# Sheet1.net
KiCad netlist of a schematic drawn in Altium Designer
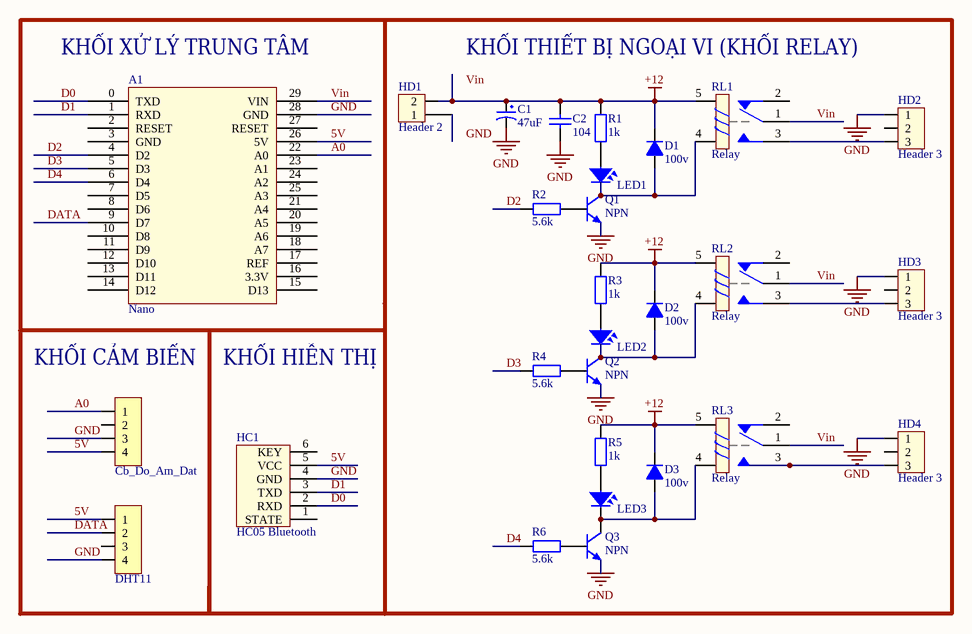
[diagram p0: Sheet1.SchDoc]

(export (version "E")
  (design (tool "Eeschema 10.0.6"))
  (components
    (comp (ref "A1")
      (value "Nano")
      (footprint "Arduino nano")
      (libsource (lib "Altium_Lib_by_KhueNguyenCreator") (part "Arduino Nano"))
    )
    (comp (ref "C1")
      (value "47uF")
      (footprint "tu hoa 5mm")
      (description "Cắm")
      (libsource (lib "Altium_Lib_by_KhueNguyenCreator") (part "Tu Hoa 47uF 25V 5x8"))
    )
    (comp (ref "C2")
      (value "104")
      (footprint "tu gom")
      (description "Cắm")
      (libsource (lib "Altium_Lib_by_KhueNguyenCreator") (part "Tu gom 104 50V"))
    )
    (comp (ref "D1")
      (value "100v")
      (footprint "DIODE 1A")
      (description "Cắm")
      (libsource (lib "Altium_Lib_by_KhueNguyenCreator") (part "Diode 1N4007"))
    )
    (comp (ref "D2")
      (value "100v")
      (footprint "DIODE 1A")
      (description "Cắm")
      (libsource (lib "Altium_Lib_by_KhueNguyenCreator") (part "Diode 1N4007"))
    )
    (comp (ref "D3")
      (value "100v")
      (footprint "DIODE 1A")
      (description "Cắm")
      (libsource (lib "Altium_Lib_by_KhueNguyenCreator") (part "Diode 1N4007"))
    )
    (comp (ref "HC1")
      (value "HC05 Bluetooth")
      (footprint "HC05 Bluethooth Dung")
      (description "Bluetooth HC05")
      (libsource (lib "Altium_Lib_by_KhueNguyenCreator") (part "HC05 Bluetooth"))
    )
    (comp (ref "HD1")
      (value "Header 2")
      (footprint "HED2")
      (description "Header 2 (Green)")
      (libsource (lib "syhaunguyen") (part "Hed2"))
    )
    (comp (ref "HD2")
      (value "Header 3")
      (footprint "HED3")
      (description "Header 3 (Green)")
      (libsource (lib "syhaunguyen") (part "Hed3"))
    )
    (comp (ref "HD3")
      (value "Header 3")
      (footprint "HED3")
      (description "Header 3 (Green)")
      (libsource (lib "syhaunguyen") (part "Hed3"))
    )
    (comp (ref "HD4")
      (value "Header 3")
      (footprint "HED3")
      (description "Header 3 (Green)")
      (libsource (lib "syhaunguyen") (part "Hed3"))
    )
    (comp (ref "JP3")
      (value "Cb_Do_Am_Dat")
      (footprint "JP 1x4 CT")
      (description "Cắm")
      (libsource (lib "Altium_Lib_by_KhueNguyenCreator") (part "JP 1x4 2.54 Cai Thang"))
    )
    (comp (ref "JP4")
      (value "DHT11")
      (footprint "JP 1x4 CT")
      (description "Cắm")
      (libsource (lib "Altium_Lib_by_KhueNguyenCreator") (part "JP 1x4 2.54 Cai Thang"))
    )
    (comp (ref "LED1")
      (value "LED")
      (footprint "LED-3")
      (description "LED Single colour Green and Red")
      (libsource (lib "syhaunguyen") (part "LED"))
    )
    (comp (ref "LED2")
      (value "LED")
      (footprint "LED-3")
      (description "LED Single colour Green and Red")
      (libsource (lib "syhaunguyen") (part "LED"))
    )
    (comp (ref "LED3")
      (value "LED")
      (footprint "LED-3")
      (description "LED Single colour Green and Red")
      (libsource (lib "syhaunguyen") (part "LED"))
    )
    (comp (ref "Q1")
      (value "NPN")
      (footprint "TRAN-LOWPOWER")
      (description "NPN General")
      (fields (field (name "PUBLISHER") "Altium Limited"))
      (libsource (lib "My library altium") (part "NPN"))
    )
    (comp (ref "Q2")
      (value "NPN")
      (footprint "TRAN-LOWPOWER")
      (description "NPN General")
      (fields (field (name "PUBLISHER") "Altium Limited"))
      (libsource (lib "My library altium") (part "NPN"))
    )
    (comp (ref "Q3")
      (value "NPN")
      (footprint "TRAN-LOWPOWER")
      (description "NPN General")
      (fields (field (name "PUBLISHER") "Altium Limited"))
      (libsource (lib "My library altium") (part "NPN"))
    )
    (comp (ref "R1")
      (value "1k")
      (footprint "tro vach 1/4w")
      (description "Cắm")
      (libsource (lib "Altium_Lib_by_KhueNguyenCreator") (part "Tro Vach 1/4W 5% 5.6k"))
    )
    (comp (ref "R2")
      (value "5.6k")
      (footprint "tro vach 1/4w")
      (description "Cắm")
      (libsource (lib "Altium_Lib_by_KhueNguyenCreator") (part "Tro Vach 1/4W 5% 5.6k"))
    )
    (comp (ref "R3")
      (value "1k")
      (footprint "tro vach 1/4w")
      (description "Cắm")
      (libsource (lib "Altium_Lib_by_KhueNguyenCreator") (part "Tro Vach 1/4W 5% 5.6k"))
    )
    (comp (ref "R4")
      (value "5.6k")
      (footprint "tro vach 1/4w")
      (description "Cắm")
      (libsource (lib "Altium_Lib_by_KhueNguyenCreator") (part "Tro Vach 1/4W 5% 5.6k"))
    )
    (comp (ref "R5")
      (value "1k")
      (footprint "tro vach 1/4w")
      (description "Cắm")
      (libsource (lib "Altium_Lib_by_KhueNguyenCreator") (part "Tro Vach 1/4W 5% 5.6k"))
    )
    (comp (ref "R6")
      (value "5.6k")
      (footprint "tro vach 1/4w")
      (description "Cắm")
      (libsource (lib "Altium_Lib_by_KhueNguyenCreator") (part "Tro Vach 1/4W 5% 5.6k"))
    )
    (comp (ref "RL1")
      (value "Relay")
      (footprint "Relay 5 Chan SRD")
      (description "Relay 5 Chan")
      (libsource (lib "Altium_Lib_by_KhueNguyenCreator") (part "Relay 5 Chan SRD"))
    )
    (comp (ref "RL2")
      (value "Relay")
      (footprint "Relay 5 Chan SRD")
      (description "Relay 5 Chan")
      (libsource (lib "Altium_Lib_by_KhueNguyenCreator") (part "Relay 5 Chan SRD"))
    )
    (comp (ref "RL3")
      (value "Relay")
      (footprint "Relay 5 Chan SRD")
      (description "Relay 5 Chan")
      (libsource (lib "Altium_Lib_by_KhueNguyenCreator") (part "Relay 5 Chan SRD"))
    )
  )
  (nets
    (net (code "1") (name "+12") (class "Default")
      (node (ref "C1") (pin "1") (pinfunction "1_1") (pintype "passive"))
      (node (ref "C2") (pin "1") (pinfunction "1_1") (pintype "passive"))
      (node (ref "D1") (pin "2") (pinfunction "K_2") (pintype "passive"))
      (node (ref "D2") (pin "2") (pinfunction "K_2") (pintype "passive"))
      (node (ref "D3") (pin "2") (pinfunction "K_2") (pintype "passive"))
      (node (ref "HD1") (pin "2") (pinfunction "2_2") (pintype "passive"))
      (node (ref "R1") (pin "1") (pinfunction "1_1") (pintype "passive"))
      (node (ref "R3") (pin "1") (pinfunction "1_1") (pintype "passive"))
      (node (ref "R5") (pin "1") (pinfunction "1_1") (pintype "passive"))
      (node (ref "RL1") (pin "5") (pinfunction "5_5") (pintype "passive"))
      (node (ref "RL2") (pin "5") (pinfunction "5_5") (pintype "passive"))
      (node (ref "RL3") (pin "5") (pinfunction "5_5") (pintype "passive"))
    )
    (net (code "2") (name "/5V") (class "Default")
      (node (ref "A1") (pin "26") (pinfunction "5V_26") (pintype "passive"))
      (node (ref "HC1") (pin "5") (pinfunction "VCC_5") (pintype "passive"))
      (node (ref "JP3") (pin "4") (pinfunction "4_4") (pintype "passive"))
      (node (ref "JP4") (pin "1") (pinfunction "1_1") (pintype "passive"))
    )
    (net (code "3") (name "/A0") (class "Default")
      (node (ref "A1") (pin "22") (pinfunction "A0_22") (pintype "passive"))
      (node (ref "JP3") (pin "1") (pinfunction "1_1") (pintype "passive"))
    )
    (net (code "4") (name "/D0") (class "Default")
      (node (ref "A1") (pin "0") (pinfunction "TXD_0") (pintype "passive"))
      (node (ref "HC1") (pin "2") (pinfunction "RXD_2") (pintype "passive"))
    )
    (net (code "5") (name "/D1") (class "Default")
      (node (ref "A1") (pin "1") (pinfunction "RXD_1") (pintype "passive"))
      (node (ref "HC1") (pin "3") (pinfunction "TXD_3") (pintype "passive"))
    )
    (net (code "6") (name "/D2") (class "Default")
      (node (ref "A1") (pin "4") (pinfunction "D2_4") (pintype "passive"))
      (node (ref "R2") (pin "2") (pinfunction "2_2") (pintype "passive"))
    )
    (net (code "7") (name "/D3") (class "Default")
      (node (ref "A1") (pin "5") (pinfunction "D3_5") (pintype "passive"))
      (node (ref "R4") (pin "2") (pinfunction "2_2") (pintype "passive"))
    )
    (net (code "8") (name "/D4") (class "Default")
      (node (ref "A1") (pin "6") (pinfunction "D4_6") (pintype "passive"))
      (node (ref "R6") (pin "2") (pinfunction "2_2") (pintype "passive"))
    )
    (net (code "9") (name "/DATA") (class "Default")
      (node (ref "A1") (pin "9") (pinfunction "D7_9") (pintype "passive"))
      (node (ref "JP4") (pin "2") (pinfunction "2_2") (pintype "passive"))
    )
    (net (code "10") (name "/Vin") (class "Default")
      (node (ref "A1") (pin "29") (pinfunction "VIN_29") (pintype "passive"))
      (node (ref "RL1") (pin "1") (pinfunction "1_1") (pintype "passive"))
      (node (ref "RL2") (pin "1") (pinfunction "1_1") (pintype "passive"))
      (node (ref "RL3") (pin "1") (pinfunction "1_1") (pintype "passive"))
    )
    (net (code "11") (name "GND") (class "Default")
      (node (ref "A1") (pin "28") (pinfunction "GND_28") (pintype "passive"))
      (node (ref "C1") (pin "2") (pinfunction "2_2") (pintype "passive"))
      (node (ref "C2") (pin "2") (pinfunction "2_2") (pintype "passive"))
      (node (ref "HC1") (pin "4") (pinfunction "GND_4") (pintype "passive"))
      (node (ref "HD2") (pin "1") (pinfunction "1_1") (pintype "passive"))
      (node (ref "HD3") (pin "1") (pinfunction "1_1") (pintype "passive"))
      (node (ref "HD4") (pin "1") (pinfunction "1_1") (pintype "passive"))
      (node (ref "JP3") (pin "3") (pinfunction "3_3") (pintype "passive"))
      (node (ref "JP4") (pin "4") (pinfunction "4_4") (pintype "passive"))
      (node (ref "Q1") (pin "3") (pinfunction "E_3") (pintype "passive"))
      (node (ref "Q2") (pin "3") (pinfunction "E_3") (pintype "passive"))
      (node (ref "Q3") (pin "3") (pinfunction "E_3") (pintype "passive"))
    )
    (net (code "12") (name "Net-(D1-A)") (class "Default")
      (node (ref "D1") (pin "1") (pinfunction "A_1") (pintype "passive"))
      (node (ref "LED1") (pin "2") (pinfunction "2_2") (pintype "passive"))
      (node (ref "Q1") (pin "2") (pinfunction "C_2") (pintype "passive"))
      (node (ref "RL1") (pin "4") (pinfunction "4_4") (pintype "passive"))
    )
    (net (code "13") (name "Net-(D2-A)") (class "Default")
      (node (ref "D2") (pin "1") (pinfunction "A_1") (pintype "passive"))
      (node (ref "LED2") (pin "2") (pinfunction "2_2") (pintype "passive"))
      (node (ref "Q2") (pin "2") (pinfunction "C_2") (pintype "passive"))
      (node (ref "RL2") (pin "4") (pinfunction "4_4") (pintype "passive"))
    )
    (net (code "14") (name "Net-(D3-A)") (class "Default")
      (node (ref "D3") (pin "1") (pinfunction "A_1") (pintype "passive"))
      (node (ref "LED3") (pin "2") (pinfunction "2_2") (pintype "passive"))
      (node (ref "Q3") (pin "2") (pinfunction "C_2") (pintype "passive"))
      (node (ref "RL3") (pin "4") (pinfunction "4_4") (pintype "passive"))
    )
    (net (code "15") (name "Net-(HD2-Pad3)") (class "Default")
      (node (ref "HD2") (pin "3") (pinfunction "3_3") (pintype "passive"))
      (node (ref "RL1") (pin "3") (pinfunction "3_3") (pintype "passive"))
    )
    (net (code "16") (name "Net-(HD3-Pad3)") (class "Default")
      (node (ref "HD3") (pin "3") (pinfunction "3_3") (pintype "passive"))
      (node (ref "RL2") (pin "3") (pinfunction "3_3") (pintype "passive"))
    )
    (net (code "17") (name "Net-(HD4-Pad3)") (class "Default")
      (node (ref "HD4") (pin "3") (pinfunction "3_3") (pintype "passive"))
      (node (ref "RL3") (pin "3") (pinfunction "3_3") (pintype "passive"))
    )
    (net (code "18") (name "Net-(LED1-Pad1)") (class "Default")
      (node (ref "LED1") (pin "1") (pinfunction "1_1") (pintype "passive"))
      (node (ref "R1") (pin "2") (pinfunction "2_2") (pintype "passive"))
    )
    (net (code "19") (name "Net-(LED2-Pad1)") (class "Default")
      (node (ref "LED2") (pin "1") (pinfunction "1_1") (pintype "passive"))
      (node (ref "R3") (pin "2") (pinfunction "2_2") (pintype "passive"))
    )
    (net (code "20") (name "Net-(LED3-Pad1)") (class "Default")
      (node (ref "LED3") (pin "1") (pinfunction "1_1") (pintype "passive"))
      (node (ref "R5") (pin "2") (pinfunction "2_2") (pintype "passive"))
    )
    (net (code "21") (name "Net-(Q1-B)") (class "Default")
      (node (ref "Q1") (pin "1") (pinfunction "B_1") (pintype "passive"))
      (node (ref "R2") (pin "1") (pinfunction "1_1") (pintype "passive"))
    )
    (net (code "22") (name "Net-(Q2-B)") (class "Default")
      (node (ref "Q2") (pin "1") (pinfunction "B_1") (pintype "passive"))
      (node (ref "R4") (pin "1") (pinfunction "1_1") (pintype "passive"))
    )
    (net (code "23") (name "Net-(Q3-B)") (class "Default")
      (node (ref "Q3") (pin "1") (pinfunction "B_1") (pintype "passive"))
      (node (ref "R6") (pin "1") (pinfunction "1_1") (pintype "passive"))
    )
    (net (code "24") (name "unconnected-(A1-3.3V-Pad16)") (class "Default")
      (node (ref "A1") (pin "16") (pinfunction "3.3V_16") (pintype "passive"))
    )
    (net (code "25") (name "unconnected-(A1-A1-Pad23)") (class "Default")
      (node (ref "A1") (pin "23") (pinfunction "A1_23") (pintype "passive"))
    )
    (net (code "26") (name "unconnected-(A1-A2-Pad24)") (class "Default")
      (node (ref "A1") (pin "24") (pinfunction "A2_24") (pintype "passive"))
    )
    (net (code "27") (name "unconnected-(A1-A3-Pad25)") (class "Default")
      (node (ref "A1") (pin "25") (pinfunction "A3_25") (pintype "passive"))
    )
    (net (code "28") (name "unconnected-(A1-A4-Pad21)") (class "Default")
      (node (ref "A1") (pin "21") (pinfunction "A4_21") (pintype "passive"))
    )
    (net (code "29") (name "unconnected-(A1-A5-Pad20)") (class "Default")
      (node (ref "A1") (pin "20") (pinfunction "A5_20") (pintype "passive"))
    )
    (net (code "30") (name "unconnected-(A1-A6-Pad19)") (class "Default")
      (node (ref "A1") (pin "19") (pinfunction "A6_19") (pintype "passive"))
    )
    (net (code "31") (name "unconnected-(A1-A7-Pad18)") (class "Default")
      (node (ref "A1") (pin "18") (pinfunction "A7_18") (pintype "passive"))
    )
    (net (code "32") (name "unconnected-(A1-D5-Pad7)") (class "Default")
      (node (ref "A1") (pin "7") (pinfunction "D5_7") (pintype "passive"))
    )
    (net (code "33") (name "unconnected-(A1-D6-Pad8)") (class "Default")
      (node (ref "A1") (pin "8") (pinfunction "D6_8") (pintype "passive"))
    )
    (net (code "34") (name "unconnected-(A1-D8-Pad10)") (class "Default")
      (node (ref "A1") (pin "10") (pinfunction "D8_10") (pintype "passive"))
    )
    (net (code "35") (name "unconnected-(A1-D9-Pad11)") (class "Default")
      (node (ref "A1") (pin "11") (pinfunction "D9_11") (pintype "passive"))
    )
    (net (code "36") (name "unconnected-(A1-D10-Pad12)") (class "Default")
      (node (ref "A1") (pin "12") (pinfunction "D10_12") (pintype "passive"))
    )
    (net (code "37") (name "unconnected-(A1-D11-Pad13)") (class "Default")
      (node (ref "A1") (pin "13") (pinfunction "D11_13") (pintype "passive"))
    )
    (net (code "38") (name "unconnected-(A1-D12-Pad14)") (class "Default")
      (node (ref "A1") (pin "14") (pinfunction "D12_14") (pintype "passive"))
    )
    (net (code "39") (name "unconnected-(A1-D13-Pad15)") (class "Default")
      (node (ref "A1") (pin "15") (pinfunction "D13_15") (pintype "passive"))
    )
    (net (code "40") (name "unconnected-(A1-GND-Pad3)") (class "Default")
      (node (ref "A1") (pin "3") (pinfunction "GND_3") (pintype "passive"))
    )
    (net (code "41") (name "unconnected-(A1-REF-Pad17)") (class "Default")
      (node (ref "A1") (pin "17") (pinfunction "REF_17") (pintype "passive"))
    )
    (net (code "42") (name "unconnected-(A1-RESET-Pad2)") (class "Default")
      (node (ref "A1") (pin "2") (pinfunction "RESET_2") (pintype "passive"))
    )
    (net (code "43") (name "unconnected-(A1-RESET-Pad27)") (class "Default")
      (node (ref "A1") (pin "27") (pinfunction "RESET_27") (pintype "passive"))
    )
    (net (code "44") (name "unconnected-(HC1-KEY-Pad6)") (class "Default")
      (node (ref "HC1") (pin "6") (pinfunction "KEY_6") (pintype "passive"))
    )
    (net (code "45") (name "unconnected-(HC1-STATE-Pad1)") (class "Default")
      (node (ref "HC1") (pin "1") (pinfunction "STATE_1") (pintype "passive"))
    )
    (net (code "46") (name "unconnected-(HD1-Pad1)") (class "Default")
      (node (ref "HD1") (pin "1") (pinfunction "1_1") (pintype "passive"))
    )
    (net (code "47") (name "unconnected-(HD2-Pad2)") (class "Default")
      (node (ref "HD2") (pin "2") (pinfunction "2_2") (pintype "passive"))
    )
    (net (code "48") (name "unconnected-(HD3-Pad2)") (class "Default")
      (node (ref "HD3") (pin "2") (pinfunction "2_2") (pintype "passive"))
    )
    (net (code "49") (name "unconnected-(HD4-Pad2)") (class "Default")
      (node (ref "HD4") (pin "2") (pinfunction "2_2") (pintype "passive"))
    )
    (net (code "50") (name "unconnected-(JP3-Pad2)") (class "Default")
      (node (ref "JP3") (pin "2") (pinfunction "2_2") (pintype "passive"))
    )
    (net (code "51") (name "unconnected-(JP4-Pad3)") (class "Default")
      (node (ref "JP4") (pin "3") (pinfunction "3_3") (pintype "passive"))
    )
    (net (code "52") (name "unconnected-(RL1-Pad2)") (class "Default")
      (node (ref "RL1") (pin "2") (pinfunction "2_2") (pintype "passive"))
    )
    (net (code "53") (name "unconnected-(RL2-Pad2)") (class "Default")
      (node (ref "RL2") (pin "2") (pinfunction "2_2") (pintype "passive"))
    )
    (net (code "54") (name "unconnected-(RL3-Pad2)") (class "Default")
      (node (ref "RL3") (pin "2") (pinfunction "2_2") (pintype "passive"))
    )
  )
)
